# sample64pin.net
KiCad netlist of a schematic drawn in EAGLE
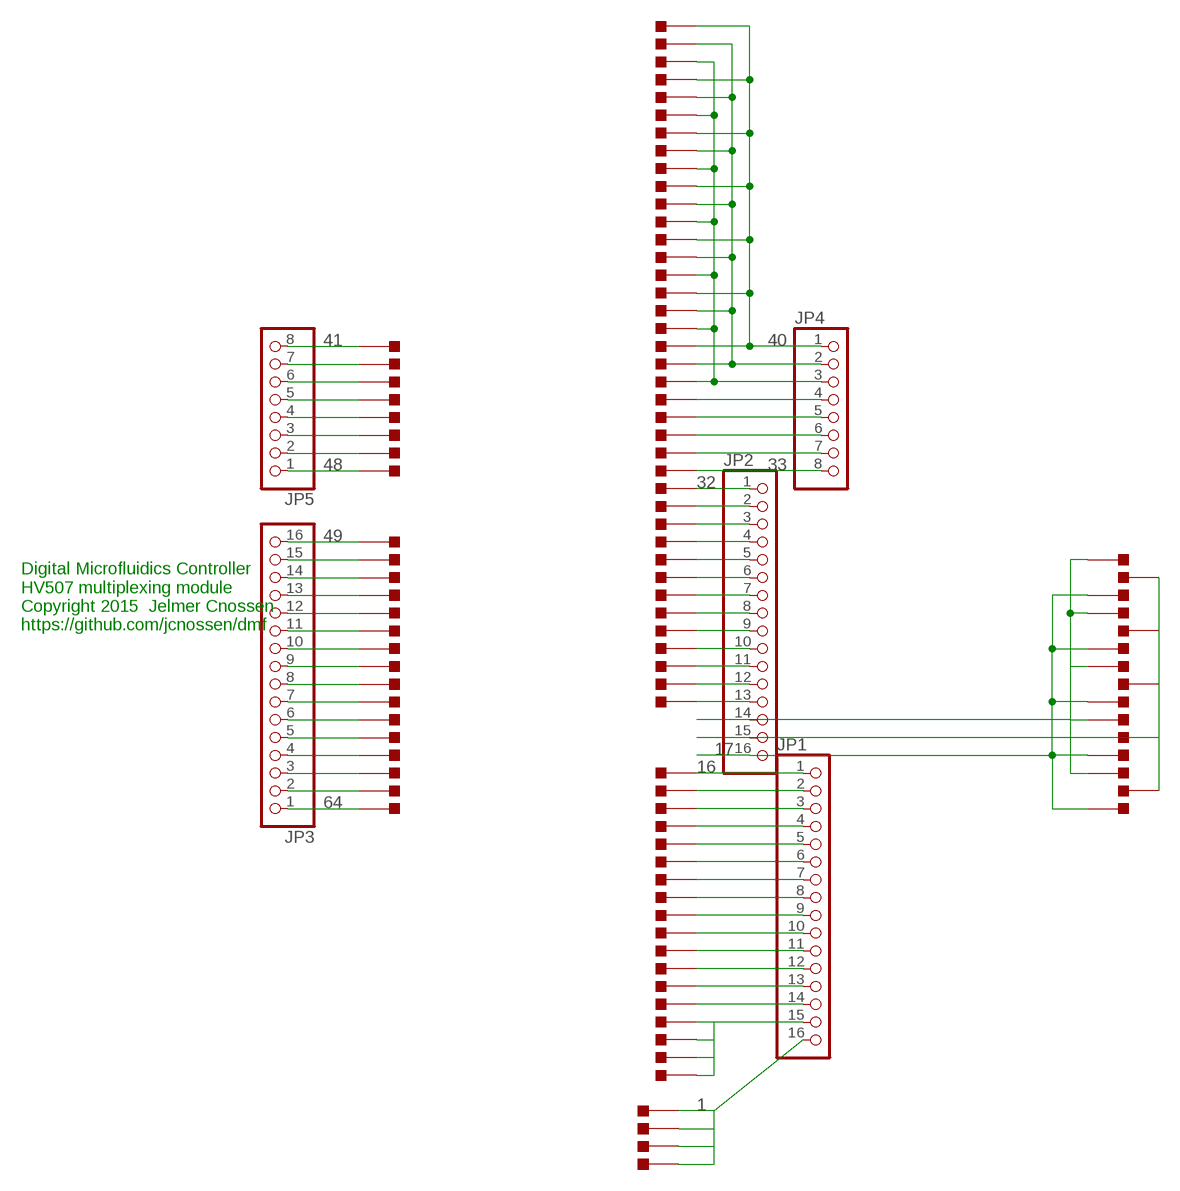
[diagram p0: schematic, sheet 1]

(export (version "E")
  (design (tool "Eeschema 10.0.6"))
  (components
    (comp (ref "JP1")
      (value "PINHD-1X16_2.54-S")
      (footprint "eagle-import:1X16-S")
      (libsource (lib "eagle-import") (part "PINHD-1X16_2.54-S"))
    )
    (comp (ref "JP2")
      (value "PINHD-1X16_2.54-S")
      (footprint "eagle-import:1X16-S")
      (libsource (lib "eagle-import") (part "PINHD-1X16_2.54-S"))
    )
    (comp (ref "JP3")
      (value "PINHD-1X16_2.54-S")
      (footprint "eagle-import:1X16-S")
      (libsource (lib "eagle-import") (part "PINHD-1X16_2.54-S"))
    )
    (comp (ref "JP4")
      (value "PINHD-1X08_2.54-S")
      (footprint "eagle-import:1X08-S")
      (libsource (lib "eagle-import") (part "PINHD-1X08_2.54-S"))
    )
    (comp (ref "JP5")
      (value "PINHD-1X08_2.54-S")
      (footprint "eagle-import:1X08-S")
      (libsource (lib "eagle-import") (part "PINHD-1X08_2.54-S"))
    )
    (comp (ref "U$1")
      (value "ELECTRODE")
      (footprint "eagle-import:ELECTRODE")
      (libsource (lib "eagle-import") (part "ELECTRODE"))
    )
    (comp (ref "U$2")
      (value "ELECTRODE")
      (footprint "eagle-import:ELECTRODE")
      (libsource (lib "eagle-import") (part "ELECTRODE"))
    )
    (comp (ref "U$3")
      (value "ELECTRODE")
      (footprint "eagle-import:ELECTRODE")
      (libsource (lib "eagle-import") (part "ELECTRODE"))
    )
    (comp (ref "U$4")
      (value "ELECTRODE")
      (footprint "eagle-import:ELECTRODE")
      (libsource (lib "eagle-import") (part "ELECTRODE"))
    )
    (comp (ref "U$5")
      (value "ELECTRODE")
      (footprint "eagle-import:ELECTRODE")
      (libsource (lib "eagle-import") (part "ELECTRODE"))
    )
    (comp (ref "U$6")
      (value "ELECTRODE")
      (footprint "eagle-import:ELECTRODE")
      (libsource (lib "eagle-import") (part "ELECTRODE"))
    )
    (comp (ref "U$7")
      (value "ELECTRODE")
      (footprint "eagle-import:ELECTRODE")
      (libsource (lib "eagle-import") (part "ELECTRODE"))
    )
    (comp (ref "U$8")
      (value "ELECTRODE")
      (footprint "eagle-import:ELECTRODE")
      (libsource (lib "eagle-import") (part "ELECTRODE"))
    )
    (comp (ref "U$9")
      (value "ELECTRODE")
      (footprint "eagle-import:ELECTRODE")
      (libsource (lib "eagle-import") (part "ELECTRODE"))
    )
    (comp (ref "U$10")
      (value "ELECTRODE")
      (footprint "eagle-import:ELECTRODE")
      (libsource (lib "eagle-import") (part "ELECTRODE"))
    )
    (comp (ref "U$11")
      (value "ELECTRODE")
      (footprint "eagle-import:ELECTRODE")
      (libsource (lib "eagle-import") (part "ELECTRODE"))
    )
    (comp (ref "U$12")
      (value "ELECTRODE")
      (footprint "eagle-import:ELECTRODE")
      (libsource (lib "eagle-import") (part "ELECTRODE"))
    )
    (comp (ref "U$13")
      (value "ELECTRODE")
      (footprint "eagle-import:ELECTRODE")
      (libsource (lib "eagle-import") (part "ELECTRODE"))
    )
    (comp (ref "U$14")
      (value "ELECTRODE")
      (footprint "eagle-import:ELECTRODE")
      (libsource (lib "eagle-import") (part "ELECTRODE"))
    )
    (comp (ref "U$15")
      (value "ELECTRODE")
      (footprint "eagle-import:ELECTRODE")
      (libsource (lib "eagle-import") (part "ELECTRODE"))
    )
    (comp (ref "U$16")
      (value "ELECTRODE")
      (footprint "eagle-import:ELECTRODE")
      (libsource (lib "eagle-import") (part "ELECTRODE"))
    )
    (comp (ref "U$17")
      (value "ELECTRODE")
      (footprint "eagle-import:ELECTRODE")
      (libsource (lib "eagle-import") (part "ELECTRODE"))
    )
    (comp (ref "U$18")
      (value "ELECTRODE")
      (footprint "eagle-import:ELECTRODE")
      (libsource (lib "eagle-import") (part "ELECTRODE"))
    )
    (comp (ref "U$19")
      (value "ELECTRODE")
      (footprint "eagle-import:ELECTRODE")
      (libsource (lib "eagle-import") (part "ELECTRODE"))
    )
    (comp (ref "U$20")
      (value "ELECTRODE")
      (footprint "eagle-import:ELECTRODE")
      (libsource (lib "eagle-import") (part "ELECTRODE"))
    )
    (comp (ref "U$21")
      (value "ELECTRODE")
      (footprint "eagle-import:ELECTRODE")
      (libsource (lib "eagle-import") (part "ELECTRODE"))
    )
    (comp (ref "U$22")
      (value "ELECTRODE")
      (footprint "eagle-import:ELECTRODE")
      (libsource (lib "eagle-import") (part "ELECTRODE"))
    )
    (comp (ref "U$23")
      (value "ELECTRODE")
      (footprint "eagle-import:ELECTRODE")
      (libsource (lib "eagle-import") (part "ELECTRODE"))
    )
    (comp (ref "U$24")
      (value "ELECTRODE")
      (footprint "eagle-import:ELECTRODE")
      (libsource (lib "eagle-import") (part "ELECTRODE"))
    )
    (comp (ref "U$25")
      (value "ELECTRODE")
      (footprint "eagle-import:ELECTRODE")
      (libsource (lib "eagle-import") (part "ELECTRODE"))
    )
    (comp (ref "U$26")
      (value "ELECTRODE")
      (footprint "eagle-import:ELECTRODE")
      (libsource (lib "eagle-import") (part "ELECTRODE"))
    )
    (comp (ref "U$27")
      (value "ELECTRODE")
      (footprint "eagle-import:ELECTRODE")
      (libsource (lib "eagle-import") (part "ELECTRODE"))
    )
    (comp (ref "U$28")
      (value "ELECTRODE")
      (footprint "eagle-import:ELECTRODE")
      (libsource (lib "eagle-import") (part "ELECTRODE"))
    )
    (comp (ref "U$29")
      (value "ELECTRODE")
      (footprint "eagle-import:ELECTRODE")
      (libsource (lib "eagle-import") (part "ELECTRODE"))
    )
    (comp (ref "U$30")
      (value "ELECTRODE")
      (footprint "eagle-import:ELECTRODE")
      (libsource (lib "eagle-import") (part "ELECTRODE"))
    )
    (comp (ref "U$31")
      (value "ELECTRODE")
      (footprint "eagle-import:ELECTRODE")
      (libsource (lib "eagle-import") (part "ELECTRODE"))
    )
    (comp (ref "U$32")
      (value "ELECTRODE")
      (footprint "eagle-import:ELECTRODE")
      (libsource (lib "eagle-import") (part "ELECTRODE"))
    )
    (comp (ref "U$33")
      (value "ELECTRODE")
      (footprint "eagle-import:ELECTRODE")
      (libsource (lib "eagle-import") (part "ELECTRODE"))
    )
    (comp (ref "U$34")
      (value "ELECTRODE")
      (footprint "eagle-import:ELECTRODE")
      (libsource (lib "eagle-import") (part "ELECTRODE"))
    )
    (comp (ref "U$35")
      (value "ELECTRODE")
      (footprint "eagle-import:ELECTRODE")
      (libsource (lib "eagle-import") (part "ELECTRODE"))
    )
    (comp (ref "U$36")
      (value "ELECTRODE")
      (footprint "eagle-import:ELECTRODE")
      (libsource (lib "eagle-import") (part "ELECTRODE"))
    )
    (comp (ref "U$37")
      (value "ELECTRODE")
      (footprint "eagle-import:ELECTRODE")
      (libsource (lib "eagle-import") (part "ELECTRODE"))
    )
    (comp (ref "U$38")
      (value "ELECTRODE")
      (footprint "eagle-import:ELECTRODE")
      (libsource (lib "eagle-import") (part "ELECTRODE"))
    )
    (comp (ref "U$39")
      (value "ELECTRODE")
      (footprint "eagle-import:ELECTRODE")
      (libsource (lib "eagle-import") (part "ELECTRODE"))
    )
    (comp (ref "U$40")
      (value "ELECTRODE")
      (footprint "eagle-import:ELECTRODE")
      (libsource (lib "eagle-import") (part "ELECTRODE"))
    )
    (comp (ref "U$41")
      (value "ELECTRODE")
      (footprint "eagle-import:ELECTRODE")
      (libsource (lib "eagle-import") (part "ELECTRODE"))
    )
    (comp (ref "U$42")
      (value "ELECTRODE")
      (footprint "eagle-import:ELECTRODE")
      (libsource (lib "eagle-import") (part "ELECTRODE"))
    )
    (comp (ref "U$43")
      (value "ELECTRODE")
      (footprint "eagle-import:ELECTRODE")
      (libsource (lib "eagle-import") (part "ELECTRODE"))
    )
    (comp (ref "U$44")
      (value "ELECTRODE")
      (footprint "eagle-import:ELECTRODE")
      (libsource (lib "eagle-import") (part "ELECTRODE"))
    )
    (comp (ref "U$45")
      (value "ELECTRODE")
      (footprint "eagle-import:ELECTRODE")
      (libsource (lib "eagle-import") (part "ELECTRODE"))
    )
    (comp (ref "U$46")
      (value "ELECTRODE")
      (footprint "eagle-import:ELECTRODE")
      (libsource (lib "eagle-import") (part "ELECTRODE"))
    )
    (comp (ref "U$47")
      (value "ELECTRODE")
      (footprint "eagle-import:ELECTRODE")
      (libsource (lib "eagle-import") (part "ELECTRODE"))
    )
    (comp (ref "U$48")
      (value "ELECTRODE")
      (footprint "eagle-import:ELECTRODE")
      (libsource (lib "eagle-import") (part "ELECTRODE"))
    )
    (comp (ref "U$49")
      (value "ELECTRODE")
      (footprint "eagle-import:ELECTRODE")
      (libsource (lib "eagle-import") (part "ELECTRODE"))
    )
    (comp (ref "U$50")
      (value "ELECTRODE")
      (footprint "eagle-import:ELECTRODE")
      (libsource (lib "eagle-import") (part "ELECTRODE"))
    )
    (comp (ref "U$51")
      (value "ELECTRODE")
      (footprint "eagle-import:ELECTRODE")
      (libsource (lib "eagle-import") (part "ELECTRODE"))
    )
    (comp (ref "U$52")
      (value "ELECTRODE")
      (footprint "eagle-import:ELECTRODE")
      (libsource (lib "eagle-import") (part "ELECTRODE"))
    )
    (comp (ref "U$53")
      (value "ELECTRODE")
      (footprint "eagle-import:ELECTRODE")
      (libsource (lib "eagle-import") (part "ELECTRODE"))
    )
    (comp (ref "U$54")
      (value "ELECTRODE")
      (footprint "eagle-import:ELECTRODE")
      (libsource (lib "eagle-import") (part "ELECTRODE"))
    )
    (comp (ref "U$55")
      (value "ELECTRODE")
      (footprint "eagle-import:ELECTRODE")
      (libsource (lib "eagle-import") (part "ELECTRODE"))
    )
    (comp (ref "U$56")
      (value "ELECTRODE")
      (footprint "eagle-import:ELECTRODE")
      (libsource (lib "eagle-import") (part "ELECTRODE"))
    )
    (comp (ref "U$57")
      (value "ELECTRODE")
      (footprint "eagle-import:ELECTRODE")
      (libsource (lib "eagle-import") (part "ELECTRODE"))
    )
    (comp (ref "U$58")
      (value "ELECTRODE")
      (footprint "eagle-import:ELECTRODE")
      (libsource (lib "eagle-import") (part "ELECTRODE"))
    )
    (comp (ref "U$59")
      (value "ELECTRODE")
      (footprint "eagle-import:ELECTRODE")
      (libsource (lib "eagle-import") (part "ELECTRODE"))
    )
    (comp (ref "U$60")
      (value "ELECTRODE")
      (footprint "eagle-import:ELECTRODE")
      (libsource (lib "eagle-import") (part "ELECTRODE"))
    )
    (comp (ref "U$61")
      (value "ELECTRODE")
      (footprint "eagle-import:ELECTRODE")
      (libsource (lib "eagle-import") (part "ELECTRODE"))
    )
    (comp (ref "U$62")
      (value "ELECTRODE")
      (footprint "eagle-import:ELECTRODE")
      (libsource (lib "eagle-import") (part "ELECTRODE"))
    )
    (comp (ref "U$63")
      (value "ELECTRODE")
      (footprint "eagle-import:ELECTRODE")
      (libsource (lib "eagle-import") (part "ELECTRODE"))
    )
    (comp (ref "U$64")
      (value "ELECTRODE")
      (footprint "eagle-import:ELECTRODE")
      (libsource (lib "eagle-import") (part "ELECTRODE"))
    )
    (comp (ref "U$65")
      (value "ELECTRODE")
      (footprint "eagle-import:ELECTRODE")
      (libsource (lib "eagle-import") (part "ELECTRODE"))
    )
    (comp (ref "U$66")
      (value "ELECTRODE")
      (footprint "eagle-import:ELECTRODE")
      (libsource (lib "eagle-import") (part "ELECTRODE"))
    )
    (comp (ref "U$67")
      (value "ELECTRODE")
      (footprint "eagle-import:ELECTRODE")
      (libsource (lib "eagle-import") (part "ELECTRODE"))
    )
    (comp (ref "U$68")
      (value "ELECTRODE")
      (footprint "eagle-import:ELECTRODE")
      (libsource (lib "eagle-import") (part "ELECTRODE"))
    )
    (comp (ref "U$69")
      (value "ELECTRODE")
      (footprint "eagle-import:ELECTRODE")
      (libsource (lib "eagle-import") (part "ELECTRODE"))
    )
    (comp (ref "U$70")
      (value "ELECTRODE")
      (footprint "eagle-import:ELECTRODE")
      (libsource (lib "eagle-import") (part "ELECTRODE"))
    )
    (comp (ref "U$71")
      (value "ELECTRODE")
      (footprint "eagle-import:ELECTRODE")
      (libsource (lib "eagle-import") (part "ELECTRODE"))
    )
    (comp (ref "U$72")
      (value "ELECTRODE")
      (footprint "eagle-import:ELECTRODE")
      (libsource (lib "eagle-import") (part "ELECTRODE"))
    )
    (comp (ref "U$73")
      (value "ELECTRODE")
      (footprint "eagle-import:ELECTRODE")
      (libsource (lib "eagle-import") (part "ELECTRODE"))
    )
    (comp (ref "U$74")
      (value "ELECTRODE")
      (footprint "eagle-import:ELECTRODE")
      (libsource (lib "eagle-import") (part "ELECTRODE"))
    )
    (comp (ref "U$75")
      (value "ELECTRODE")
      (footprint "eagle-import:ELECTRODE")
      (libsource (lib "eagle-import") (part "ELECTRODE"))
    )
    (comp (ref "U$76")
      (value "ELECTRODE")
      (footprint "eagle-import:ELECTRODE")
      (libsource (lib "eagle-import") (part "ELECTRODE"))
    )
    (comp (ref "U$77")
      (value "ELECTRODE")
      (footprint "eagle-import:ELECTRODE")
      (libsource (lib "eagle-import") (part "ELECTRODE"))
    )
    (comp (ref "U$78")
      (value "ELECTRODE")
      (footprint "eagle-import:ELECTRODE")
      (libsource (lib "eagle-import") (part "ELECTRODE"))
    )
    (comp (ref "U$79")
      (value "ELECTRODE")
      (footprint "eagle-import:ELECTRODE")
      (libsource (lib "eagle-import") (part "ELECTRODE"))
    )
    (comp (ref "U$80")
      (value "ELECTRODE")
      (footprint "eagle-import:ELECTRODE")
      (libsource (lib "eagle-import") (part "ELECTRODE"))
    )
    (comp (ref "U$81")
      (value "ELECTRODE")
      (footprint "eagle-import:ELECTRODE")
      (libsource (lib "eagle-import") (part "ELECTRODE"))
    )
    (comp (ref "U$82")
      (value "ELECTRODE")
      (footprint "eagle-import:ELECTRODE")
      (libsource (lib "eagle-import") (part "ELECTRODE"))
    )
    (comp (ref "U$83")
      (value "ELECTRODE")
      (footprint "eagle-import:ELECTRODE")
      (libsource (lib "eagle-import") (part "ELECTRODE"))
    )
    (comp (ref "U$84")
      (value "ELECTRODE")
      (footprint "eagle-import:ELECTRODE")
      (libsource (lib "eagle-import") (part "ELECTRODE"))
    )
    (comp (ref "U$85")
      (value "ELECTRODE")
      (footprint "eagle-import:ELECTRODE")
      (libsource (lib "eagle-import") (part "ELECTRODE"))
    )
    (comp (ref "U$86")
      (value "ELECTRODE")
      (footprint "eagle-import:ELECTRODE")
      (libsource (lib "eagle-import") (part "ELECTRODE"))
    )
    (comp (ref "U$87")
      (value "ELECTRODE")
      (footprint "eagle-import:ELECTRODE")
      (libsource (lib "eagle-import") (part "ELECTRODE"))
    )
    (comp (ref "U$88")
      (value "ELECTRODE")
      (footprint "eagle-import:ELECTRODE")
      (libsource (lib "eagle-import") (part "ELECTRODE"))
    )
    (comp (ref "U$89")
      (value "ELECTRODE")
      (footprint "eagle-import:ELECTRODE")
      (libsource (lib "eagle-import") (part "ELECTRODE"))
    )
    (comp (ref "U$90")
      (value "ELECTRODE")
      (footprint "eagle-import:ELECTRODE")
      (libsource (lib "eagle-import") (part "ELECTRODE"))
    )
    (comp (ref "U$91")
      (value "ELECTRODE")
      (footprint "eagle-import:ELECTRODE")
      (libsource (lib "eagle-import") (part "ELECTRODE"))
    )
    (comp (ref "U$92")
      (value "ELECTRODE")
      (footprint "eagle-import:ELECTRODE")
      (libsource (lib "eagle-import") (part "ELECTRODE"))
    )
    (comp (ref "U$93")
      (value "ELECTRODE")
      (footprint "eagle-import:ELECTRODE")
      (libsource (lib "eagle-import") (part "ELECTRODE"))
    )
    (comp (ref "U$94")
      (value "ELECTRODE")
      (footprint "eagle-import:ELECTRODE")
      (libsource (lib "eagle-import") (part "ELECTRODE"))
    )
    (comp (ref "U$95")
      (value "ELECTRODE")
      (footprint "eagle-import:ELECTRODE")
      (libsource (lib "eagle-import") (part "ELECTRODE"))
    )
    (comp (ref "U$96")
      (value "ELECTRODE")
      (footprint "eagle-import:ELECTRODE")
      (libsource (lib "eagle-import") (part "ELECTRODE"))
    )
    (comp (ref "U$97")
      (value "ELECTRODE")
      (footprint "eagle-import:ELECTRODE")
      (libsource (lib "eagle-import") (part "ELECTRODE"))
    )
    (comp (ref "U$98")
      (value "ELECTRODE")
      (footprint "eagle-import:ELECTRODE")
      (libsource (lib "eagle-import") (part "ELECTRODE"))
    )
    (comp (ref "U$99")
      (value "ELECTRODE")
      (footprint "eagle-import:ELECTRODE")
      (libsource (lib "eagle-import") (part "ELECTRODE"))
    )
    (comp (ref "U$100")
      (value "ELECTRODE")
      (footprint "eagle-import:ELECTRODE")
      (libsource (lib "eagle-import") (part "ELECTRODE"))
    )
  )
  (nets
    (net (code "1") (name "/1") (class "Default")
      (node (ref "JP1") (pin "16") (pinfunction "16_16") (pintype "passive"))
      (node (ref "U$46") (pin "P$2") (pinfunction "E_P$2") (pintype "bidirectional"))
      (node (ref "U$47") (pin "P$2") (pinfunction "E_P$2") (pintype "bidirectional"))
      (node (ref "U$48") (pin "P$2") (pinfunction "E_P$2") (pintype "bidirectional"))
      (node (ref "U$64") (pin "P$2") (pinfunction "E_P$2") (pintype "bidirectional"))
    )
    (net (code "2") (name "/16") (class "Default")
      (node (ref "JP1") (pin "1") (pinfunction "1_1") (pintype "passive"))
      (node (ref "U$49") (pin "P$2") (pinfunction "E_P$2") (pintype "bidirectional"))
    )
    (net (code "3") (name "/17") (class "Default")
      (node (ref "JP2") (pin "16") (pinfunction "16_16") (pintype "passive"))
      (node (ref "U$67") (pin "P$2") (pinfunction "E_P$2") (pintype "bidirectional"))
      (node (ref "U$70") (pin "P$2") (pinfunction "E_P$2") (pintype "bidirectional"))
      (node (ref "U$73") (pin "P$2") (pinfunction "E_P$2") (pintype "bidirectional"))
      (node (ref "U$76") (pin "P$2") (pinfunction "E_P$2") (pintype "bidirectional"))
      (node (ref "U$79") (pin "P$2") (pinfunction "E_P$2") (pintype "bidirectional"))
    )
    (net (code "4") (name "/32") (class "Default")
      (node (ref "JP2") (pin "1") (pinfunction "1_1") (pintype "passive"))
      (node (ref "U$33") (pin "P$2") (pinfunction "E_P$2") (pintype "bidirectional"))
    )
    (net (code "5") (name "/33") (class "Default")
      (node (ref "JP4") (pin "8") (pinfunction "8_8") (pintype "passive"))
      (node (ref "U$32") (pin "P$2") (pinfunction "E_P$2") (pintype "bidirectional"))
    )
    (net (code "6") (name "/40") (class "Default")
      (node (ref "JP4") (pin "1") (pinfunction "1_1") (pintype "passive"))
      (node (ref "U$1") (pin "P$2") (pinfunction "E_P$2") (pintype "bidirectional"))
      (node (ref "U$80") (pin "P$2") (pinfunction "E_P$2") (pintype "bidirectional"))
      (node (ref "U$83") (pin "P$2") (pinfunction "E_P$2") (pintype "bidirectional"))
      (node (ref "U$86") (pin "P$2") (pinfunction "E_P$2") (pintype "bidirectional"))
      (node (ref "U$89") (pin "P$2") (pinfunction "E_P$2") (pintype "bidirectional"))
      (node (ref "U$92") (pin "P$2") (pinfunction "E_P$2") (pintype "bidirectional"))
      (node (ref "U$95") (pin "P$2") (pinfunction "E_P$2") (pintype "bidirectional"))
    )
    (net (code "7") (name "/41") (class "Default")
      (node (ref "JP5") (pin "8") (pinfunction "8_8") (pintype "passive"))
      (node (ref "U$4") (pin "P$2") (pinfunction "E_P$2") (pintype "bidirectional"))
    )
    (net (code "8") (name "/48") (class "Default")
      (node (ref "JP5") (pin "1") (pinfunction "1_1") (pintype "passive"))
      (node (ref "U$11") (pin "P$2") (pinfunction "E_P$2") (pintype "bidirectional"))
    )
    (net (code "9") (name "/49") (class "Default")
      (node (ref "JP3") (pin "16") (pinfunction "16_16") (pintype "passive"))
      (node (ref "U$12") (pin "P$2") (pinfunction "E_P$2") (pintype "bidirectional"))
    )
    (net (code "10") (name "/64") (class "Default")
      (node (ref "JP3") (pin "1") (pinfunction "1_1") (pintype "passive"))
      (node (ref "U$27") (pin "P$2") (pinfunction "E_P$2") (pintype "bidirectional"))
    )
    (net (code "11") (name "Net-(U$2-E)") (class "Default")
      (node (ref "JP4") (pin "2") (pinfunction "2_2") (pintype "passive"))
      (node (ref "U$2") (pin "P$2") (pinfunction "E_P$2") (pintype "bidirectional"))
      (node (ref "U$81") (pin "P$2") (pinfunction "E_P$2") (pintype "bidirectional"))
      (node (ref "U$84") (pin "P$2") (pinfunction "E_P$2") (pintype "bidirectional"))
      (node (ref "U$87") (pin "P$2") (pinfunction "E_P$2") (pintype "bidirectional"))
      (node (ref "U$90") (pin "P$2") (pinfunction "E_P$2") (pintype "bidirectional"))
      (node (ref "U$93") (pin "P$2") (pinfunction "E_P$2") (pintype "bidirectional"))
      (node (ref "U$96") (pin "P$2") (pinfunction "E_P$2") (pintype "bidirectional"))
    )
    (net (code "12") (name "Net-(U$3-E)") (class "Default")
      (node (ref "JP4") (pin "3") (pinfunction "3_3") (pintype "passive"))
      (node (ref "U$3") (pin "P$2") (pinfunction "E_P$2") (pintype "bidirectional"))
      (node (ref "U$82") (pin "P$2") (pinfunction "E_P$2") (pintype "bidirectional"))
      (node (ref "U$85") (pin "P$2") (pinfunction "E_P$2") (pintype "bidirectional"))
      (node (ref "U$88") (pin "P$2") (pinfunction "E_P$2") (pintype "bidirectional"))
      (node (ref "U$91") (pin "P$2") (pinfunction "E_P$2") (pintype "bidirectional"))
      (node (ref "U$94") (pin "P$2") (pinfunction "E_P$2") (pintype "bidirectional"))
      (node (ref "U$97") (pin "P$2") (pinfunction "E_P$2") (pintype "bidirectional"))
    )
    (net (code "13") (name "Net-(U$5-E)") (class "Default")
      (node (ref "JP5") (pin "7") (pinfunction "7_7") (pintype "passive"))
      (node (ref "U$5") (pin "P$2") (pinfunction "E_P$2") (pintype "bidirectional"))
    )
    (net (code "14") (name "Net-(U$6-E)") (class "Default")
      (node (ref "JP5") (pin "6") (pinfunction "6_6") (pintype "passive"))
      (node (ref "U$6") (pin "P$2") (pinfunction "E_P$2") (pintype "bidirectional"))
    )
    (net (code "15") (name "Net-(U$7-E)") (class "Default")
      (node (ref "JP5") (pin "5") (pinfunction "5_5") (pintype "passive"))
      (node (ref "U$7") (pin "P$2") (pinfunction "E_P$2") (pintype "bidirectional"))
    )
    (net (code "16") (name "Net-(U$8-E)") (class "Default")
      (node (ref "JP5") (pin "4") (pinfunction "4_4") (pintype "passive"))
      (node (ref "U$8") (pin "P$2") (pinfunction "E_P$2") (pintype "bidirectional"))
    )
    (net (code "17") (name "Net-(U$9-E)") (class "Default")
      (node (ref "JP5") (pin "3") (pinfunction "3_3") (pintype "passive"))
      (node (ref "U$9") (pin "P$2") (pinfunction "E_P$2") (pintype "bidirectional"))
    )
    (net (code "18") (name "Net-(U$10-E)") (class "Default")
      (node (ref "JP5") (pin "2") (pinfunction "2_2") (pintype "passive"))
      (node (ref "U$10") (pin "P$2") (pinfunction "E_P$2") (pintype "bidirectional"))
    )
    (net (code "19") (name "Net-(U$13-E)") (class "Default")
      (node (ref "JP3") (pin "15") (pinfunction "15_15") (pintype "passive"))
      (node (ref "U$13") (pin "P$2") (pinfunction "E_P$2") (pintype "bidirectional"))
    )
    (net (code "20") (name "Net-(U$14-E)") (class "Default")
      (node (ref "JP3") (pin "14") (pinfunction "14_14") (pintype "passive"))
      (node (ref "U$14") (pin "P$2") (pinfunction "E_P$2") (pintype "bidirectional"))
    )
    (net (code "21") (name "Net-(U$15-E)") (class "Default")
      (node (ref "JP3") (pin "13") (pinfunction "13_13") (pintype "passive"))
      (node (ref "U$15") (pin "P$2") (pinfunction "E_P$2") (pintype "bidirectional"))
    )
    (net (code "22") (name "Net-(U$16-E)") (class "Default")
      (node (ref "JP3") (pin "12") (pinfunction "12_12") (pintype "passive"))
      (node (ref "U$16") (pin "P$2") (pinfunction "E_P$2") (pintype "bidirectional"))
    )
    (net (code "23") (name "Net-(U$17-E)") (class "Default")
      (node (ref "JP3") (pin "11") (pinfunction "11_11") (pintype "passive"))
      (node (ref "U$17") (pin "P$2") (pinfunction "E_P$2") (pintype "bidirectional"))
    )
    (net (code "24") (name "Net-(U$18-E)") (class "Default")
      (node (ref "JP3") (pin "10") (pinfunction "10_10") (pintype "passive"))
      (node (ref "U$18") (pin "P$2") (pinfunction "E_P$2") (pintype "bidirectional"))
    )
    (net (code "25") (name "Net-(U$19-E)") (class "Default")
      (node (ref "JP3") (pin "9") (pinfunction "9_9") (pintype "passive"))
      (node (ref "U$19") (pin "P$2") (pinfunction "E_P$2") (pintype "bidirectional"))
    )
    (net (code "26") (name "Net-(U$20-E)") (class "Default")
      (node (ref "JP3") (pin "8") (pinfunction "8_8") (pintype "passive"))
      (node (ref "U$20") (pin "P$2") (pinfunction "E_P$2") (pintype "bidirectional"))
    )
    (net (code "27") (name "Net-(U$21-E)") (class "Default")
      (node (ref "JP3") (pin "7") (pinfunction "7_7") (pintype "passive"))
      (node (ref "U$21") (pin "P$2") (pinfunction "E_P$2") (pintype "bidirectional"))
    )
    (net (code "28") (name "Net-(U$22-E)") (class "Default")
      (node (ref "JP3") (pin "6") (pinfunction "6_6") (pintype "passive"))
      (node (ref "U$22") (pin "P$2") (pinfunction "E_P$2") (pintype "bidirectional"))
    )
    (net (code "29") (name "Net-(U$23-E)") (class "Default")
      (node (ref "JP3") (pin "5") (pinfunction "5_5") (pintype "passive"))
      (node (ref "U$23") (pin "P$2") (pinfunction "E_P$2") (pintype "bidirectional"))
    )
    (net (code "30") (name "Net-(U$24-E)") (class "Default")
      (node (ref "JP3") (pin "4") (pinfunction "4_4") (pintype "passive"))
      (node (ref "U$24") (pin "P$2") (pinfunction "E_P$2") (pintype "bidirectional"))
    )
    (net (code "31") (name "Net-(U$25-E)") (class "Default")
      (node (ref "JP3") (pin "3") (pinfunction "3_3") (pintype "passive"))
      (node (ref "U$25") (pin "P$2") (pinfunction "E_P$2") (pintype "bidirectional"))
    )
    (net (code "32") (name "Net-(U$26-E)") (class "Default")
      (node (ref "JP3") (pin "2") (pinfunction "2_2") (pintype "passive"))
      (node (ref "U$26") (pin "P$2") (pinfunction "E_P$2") (pintype "bidirectional"))
    )
    (net (code "33") (name "Net-(U$28-E)") (class "Default")
      (node (ref "JP4") (pin "4") (pinfunction "4_4") (pintype "passive"))
      (node (ref "U$28") (pin "P$2") (pinfunction "E_P$2") (pintype "bidirectional"))
    )
    (net (code "34") (name "Net-(U$29-E)") (class "Default")
      (node (ref "JP4") (pin "5") (pinfunction "5_5") (pintype "passive"))
      (node (ref "U$29") (pin "P$2") (pinfunction "E_P$2") (pintype "bidirectional"))
    )
    (net (code "35") (name "Net-(U$30-E)") (class "Default")
      (node (ref "JP4") (pin "6") (pinfunction "6_6") (pintype "passive"))
      (node (ref "U$30") (pin "P$2") (pinfunction "E_P$2") (pintype "bidirectional"))
    )
    (net (code "36") (name "Net-(U$31-E)") (class "Default")
      (node (ref "JP4") (pin "7") (pinfunction "7_7") (pintype "passive"))
      (node (ref "U$31") (pin "P$2") (pinfunction "E_P$2") (pintype "bidirectional"))
    )
    (net (code "37") (name "Net-(U$34-E)") (class "Default")
      (node (ref "JP2") (pin "2") (pinfunction "2_2") (pintype "passive"))
      (node (ref "U$34") (pin "P$2") (pinfunction "E_P$2") (pintype "bidirectional"))
    )
    (net (code "38") (name "Net-(U$35-E)") (class "Default")
      (node (ref "JP2") (pin "3") (pinfunction "3_3") (pintype "passive"))
      (node (ref "U$35") (pin "P$2") (pinfunction "E_P$2") (pintype "bidirectional"))
    )
    (net (code "39") (name "Net-(U$36-E)") (class "Default")
      (node (ref "JP2") (pin "4") (pinfunction "4_4") (pintype "passive"))
      (node (ref "U$36") (pin "P$2") (pinfunction "E_P$2") (pintype "bidirectional"))
    )
    (net (code "40") (name "Net-(U$37-E)") (class "Default")
      (node (ref "JP2") (pin "5") (pinfunction "5_5") (pintype "passive"))
      (node (ref "U$37") (pin "P$2") (pinfunction "E_P$2") (pintype "bidirectional"))
    )
    (net (code "41") (name "Net-(U$38-E)") (class "Default")
      (node (ref "JP2") (pin "6") (pinfunction "6_6") (pintype "passive"))
      (node (ref "U$38") (pin "P$2") (pinfunction "E_P$2") (pintype "bidirectional"))
    )
    (net (code "42") (name "Net-(U$39-E)") (class "Default")
      (node (ref "JP2") (pin "7") (pinfunction "7_7") (pintype "passive"))
      (node (ref "U$39") (pin "P$2") (pinfunction "E_P$2") (pintype "bidirectional"))
    )
    (net (code "43") (name "Net-(U$40-E)") (class "Default")
      (node (ref "JP2") (pin "8") (pinfunction "8_8") (pintype "passive"))
      (node (ref "U$40") (pin "P$2") (pinfunction "E_P$2") (pintype "bidirectional"))
    )
    (net (code "44") (name "Net-(U$41-E)") (class "Default")
      (node (ref "JP2") (pin "9") (pinfunction "9_9") (pintype "passive"))
      (node (ref "U$41") (pin "P$2") (pinfunction "E_P$2") (pintype "bidirectional"))
    )
    (net (code "45") (name "Net-(U$42-E)") (class "Default")
      (node (ref "JP2") (pin "10") (pinfunction "10_10") (pintype "passive"))
      (node (ref "U$42") (pin "P$2") (pinfunction "E_P$2") (pintype "bidirectional"))
    )
    (net (code "46") (name "Net-(U$43-E)") (class "Default")
      (node (ref "JP2") (pin "11") (pinfunction "11_11") (pintype "passive"))
      (node (ref "U$43") (pin "P$2") (pinfunction "E_P$2") (pintype "bidirectional"))
    )
    (net (code "47") (name "Net-(U$44-E)") (class "Default")
      (node (ref "JP2") (pin "12") (pinfunction "12_12") (pintype "passive"))
      (node (ref "U$44") (pin "P$2") (pinfunction "E_P$2") (pintype "bidirectional"))
    )
    (net (code "48") (name "Net-(U$45-E)") (class "Default")
      (node (ref "JP2") (pin "13") (pinfunction "13_13") (pintype "passive"))
      (node (ref "U$45") (pin "P$2") (pinfunction "E_P$2") (pintype "bidirectional"))
    )
    (net (code "49") (name "Net-(U$50-E)") (class "Default")
      (node (ref "JP1") (pin "2") (pinfunction "2_2") (pintype "passive"))
      (node (ref "U$50") (pin "P$2") (pinfunction "E_P$2") (pintype "bidirectional"))
    )
    (net (code "50") (name "Net-(U$51-E)") (class "Default")
      (node (ref "JP1") (pin "3") (pinfunction "3_3") (pintype "passive"))
      (node (ref "U$51") (pin "P$2") (pinfunction "E_P$2") (pintype "bidirectional"))
    )
    (net (code "51") (name "Net-(U$52-E)") (class "Default")
      (node (ref "JP1") (pin "4") (pinfunction "4_4") (pintype "passive"))
      (node (ref "U$52") (pin "P$2") (pinfunction "E_P$2") (pintype "bidirectional"))
    )
    (net (code "52") (name "Net-(U$53-E)") (class "Default")
      (node (ref "JP1") (pin "5") (pinfunction "5_5") (pintype "passive"))
      (node (ref "U$53") (pin "P$2") (pinfunction "E_P$2") (pintype "bidirectional"))
    )
    (net (code "53") (name "Net-(U$54-E)") (class "Default")
      (node (ref "JP1") (pin "6") (pinfunction "6_6") (pintype "passive"))
      (node (ref "U$54") (pin "P$2") (pinfunction "E_P$2") (pintype "bidirectional"))
    )
    (net (code "54") (name "Net-(U$55-E)") (class "Default")
      (node (ref "JP1") (pin "7") (pinfunction "7_7") (pintype "passive"))
      (node (ref "U$55") (pin "P$2") (pinfunction "E_P$2") (pintype "bidirectional"))
    )
    (net (code "55") (name "Net-(U$56-E)") (class "Default")
      (node (ref "JP1") (pin "8") (pinfunction "8_8") (pintype "passive"))
      (node (ref "U$56") (pin "P$2") (pinfunction "E_P$2") (pintype "bidirectional"))
    )
    (net (code "56") (name "Net-(U$57-E)") (class "Default")
      (node (ref "JP1") (pin "9") (pinfunction "9_9") (pintype "passive"))
      (node (ref "U$57") (pin "P$2") (pinfunction "E_P$2") (pintype "bidirectional"))
    )
    (net (code "57") (name "Net-(U$58-E)") (class "Default")
      (node (ref "JP1") (pin "10") (pinfunction "10_10") (pintype "passive"))
      (node (ref "U$58") (pin "P$2") (pinfunction "E_P$2") (pintype "bidirectional"))
    )
    (net (code "58") (name "Net-(U$59-E)") (class "Default")
      (node (ref "JP1") (pin "11") (pinfunction "11_11") (pintype "passive"))
      (node (ref "U$59") (pin "P$2") (pinfunction "E_P$2") (pintype "bidirectional"))
    )
    (net (code "59") (name "Net-(U$60-E)") (class "Default")
      (node (ref "JP1") (pin "12") (pinfunction "12_12") (pintype "passive"))
      (node (ref "U$60") (pin "P$2") (pinfunction "E_P$2") (pintype "bidirectional"))
    )
    (net (code "60") (name "Net-(U$61-E)") (class "Default")
      (node (ref "JP1") (pin "13") (pinfunction "13_13") (pintype "passive"))
      (node (ref "U$61") (pin "P$2") (pinfunction "E_P$2") (pintype "bidirectional"))
    )
    (net (code "61") (name "Net-(U$62-E)") (class "Default")
      (node (ref "JP1") (pin "14") (pinfunction "14_14") (pintype "passive"))
      (node (ref "U$62") (pin "P$2") (pinfunction "E_P$2") (pintype "bidirectional"))
    )
    (net (code "62") (name "Net-(U$65-E)") (class "Default")
      (node (ref "JP2") (pin "14") (pinfunction "14_14") (pintype "passive"))
      (node (ref "U$65") (pin "P$2") (pinfunction "E_P$2") (pintype "bidirectional"))
      (node (ref "U$68") (pin "P$2") (pinfunction "E_P$2") (pintype "bidirectional"))
      (node (ref "U$71") (pin "P$2") (pinfunction "E_P$2") (pintype "bidirectional"))
      (node (ref "U$74") (pin "P$2") (pinfunction "E_P$2") (pintype "bidirectional"))
      (node (ref "U$77") (pin "P$2") (pinfunction "E_P$2") (pintype "bidirectional"))
    )
    (net (code "63") (name "Net-(U$66-E)") (class "Default")
      (node (ref "JP2") (pin "15") (pinfunction "15_15") (pintype "passive"))
      (node (ref "U$66") (pin "P$2") (pinfunction "E_P$2") (pintype "bidirectional"))
      (node (ref "U$69") (pin "P$2") (pinfunction "E_P$2") (pintype "bidirectional"))
      (node (ref "U$72") (pin "P$2") (pinfunction "E_P$2") (pintype "bidirectional"))
      (node (ref "U$75") (pin "P$2") (pinfunction "E_P$2") (pintype "bidirectional"))
      (node (ref "U$78") (pin "P$2") (pinfunction "E_P$2") (pintype "bidirectional"))
    )
    (net (code "64") (name "Net-(U$100-E)") (class "Default")
      (node (ref "JP1") (pin "15") (pinfunction "15_15") (pintype "passive"))
      (node (ref "U$100") (pin "P$2") (pinfunction "E_P$2") (pintype "bidirectional"))
      (node (ref "U$63") (pin "P$2") (pinfunction "E_P$2") (pintype "bidirectional"))
      (node (ref "U$98") (pin "P$2") (pinfunction "E_P$2") (pintype "bidirectional"))
      (node (ref "U$99") (pin "P$2") (pinfunction "E_P$2") (pintype "bidirectional"))
    )
  )
)
